# UV_Watch_1.net
KiCad netlist of a schematic drawn in Altium Designer
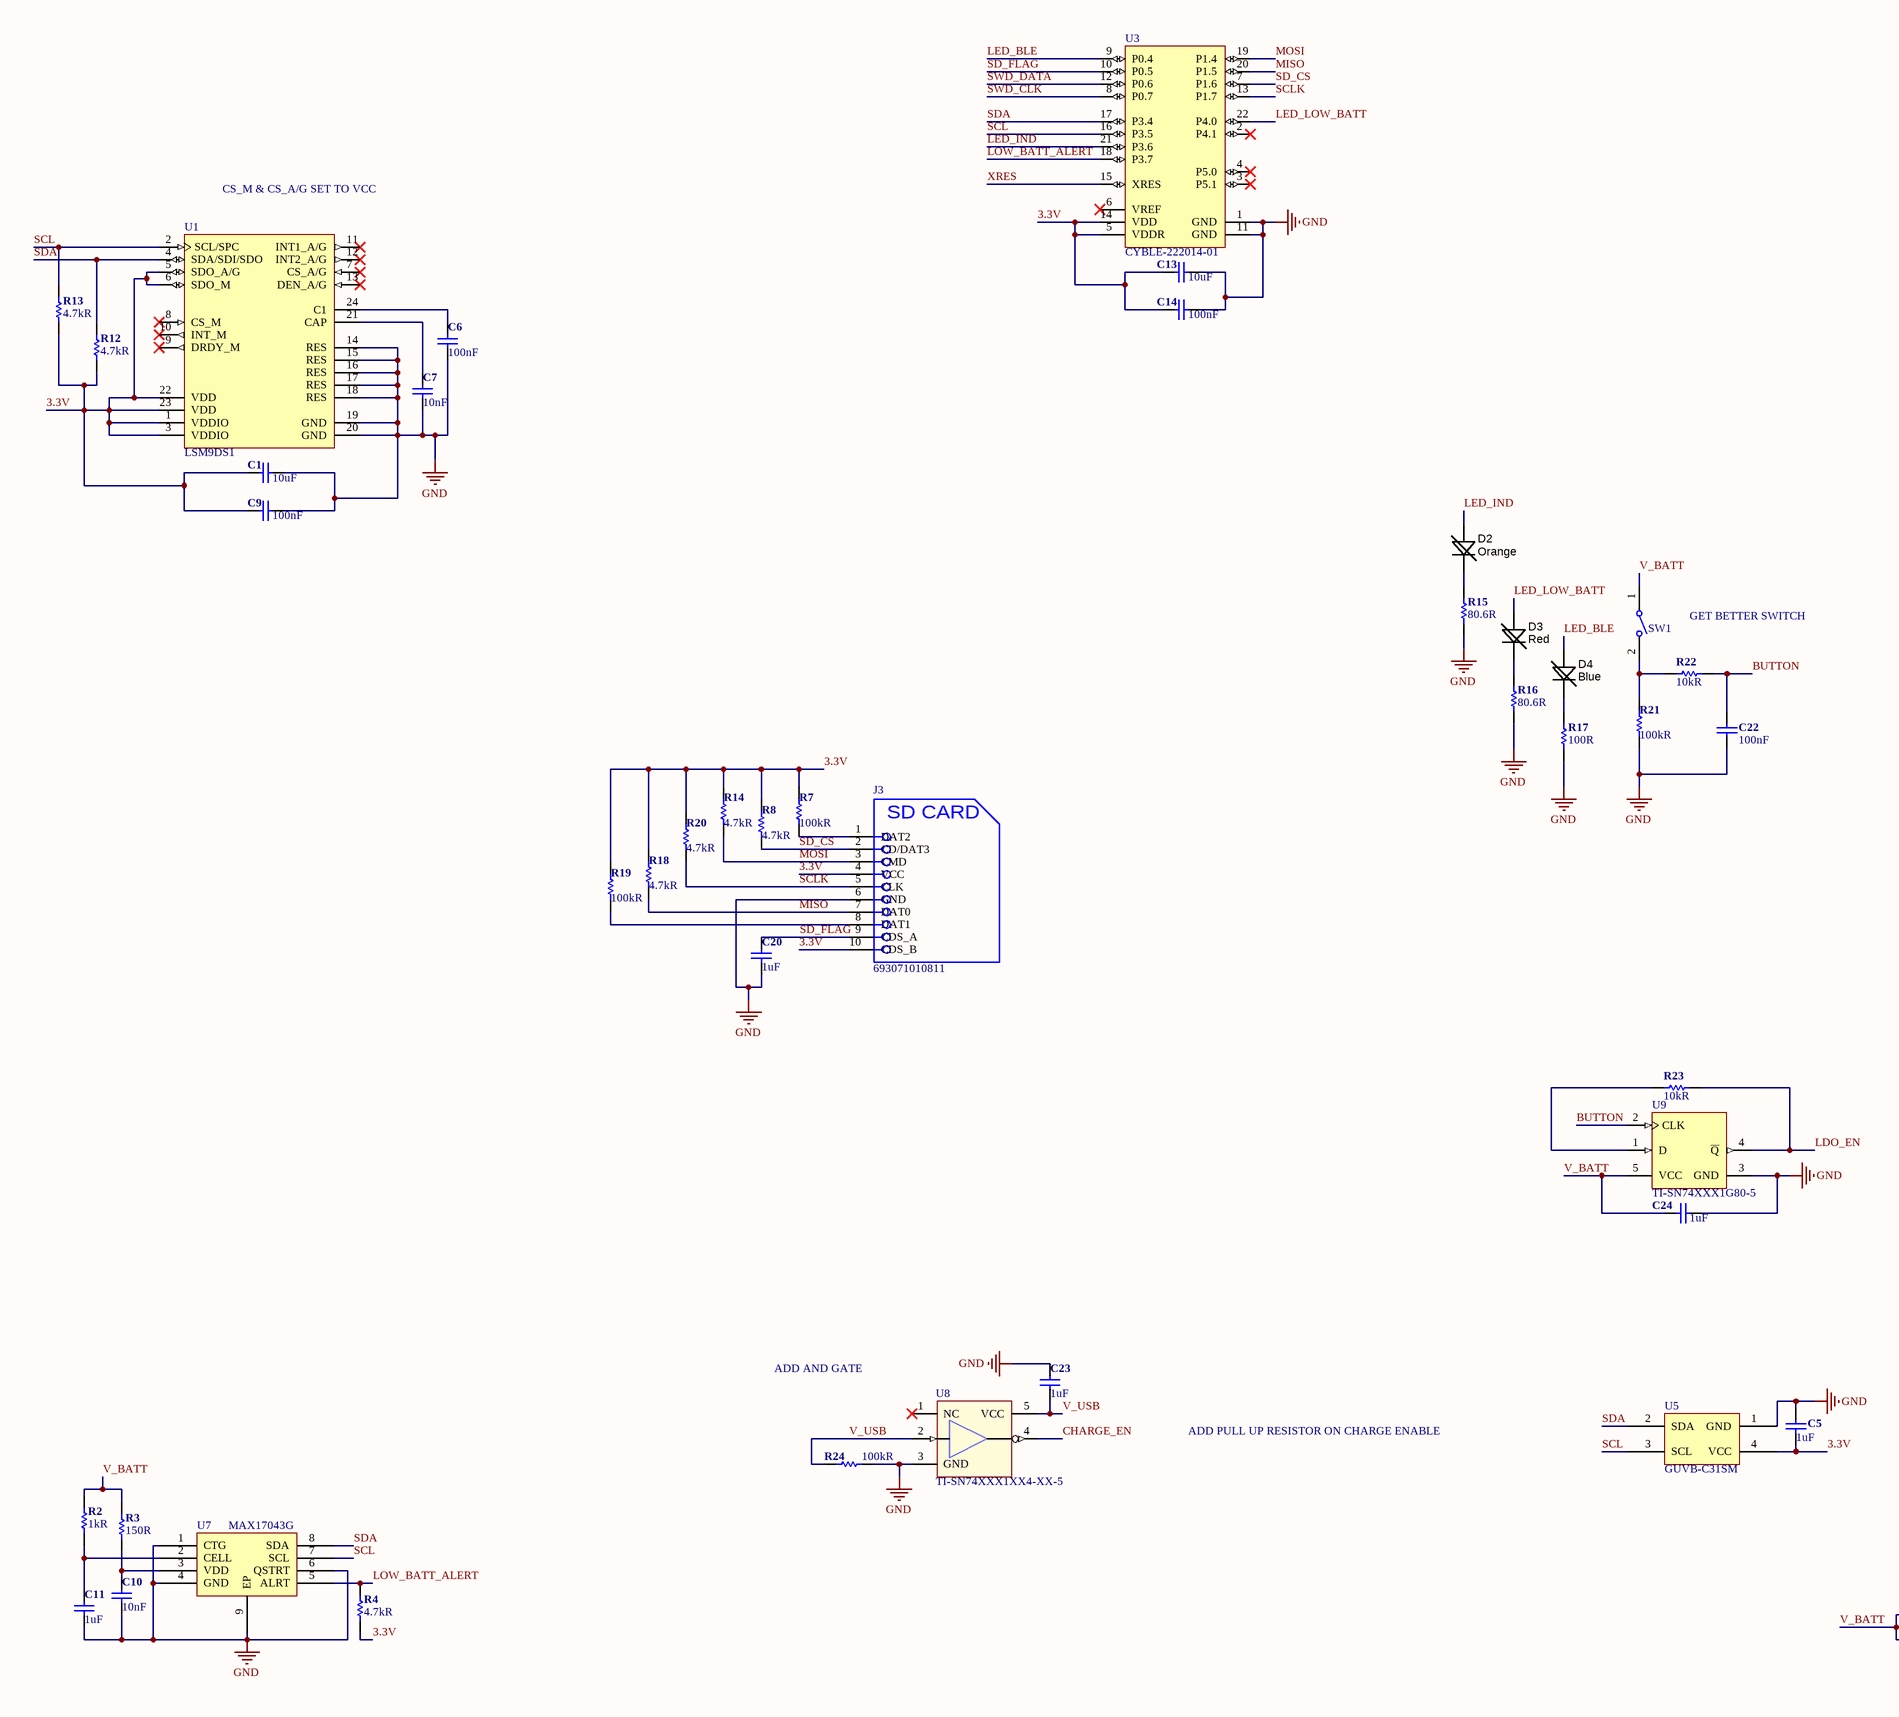
[diagram p0: UV_Watch_1.SchDoc, left]
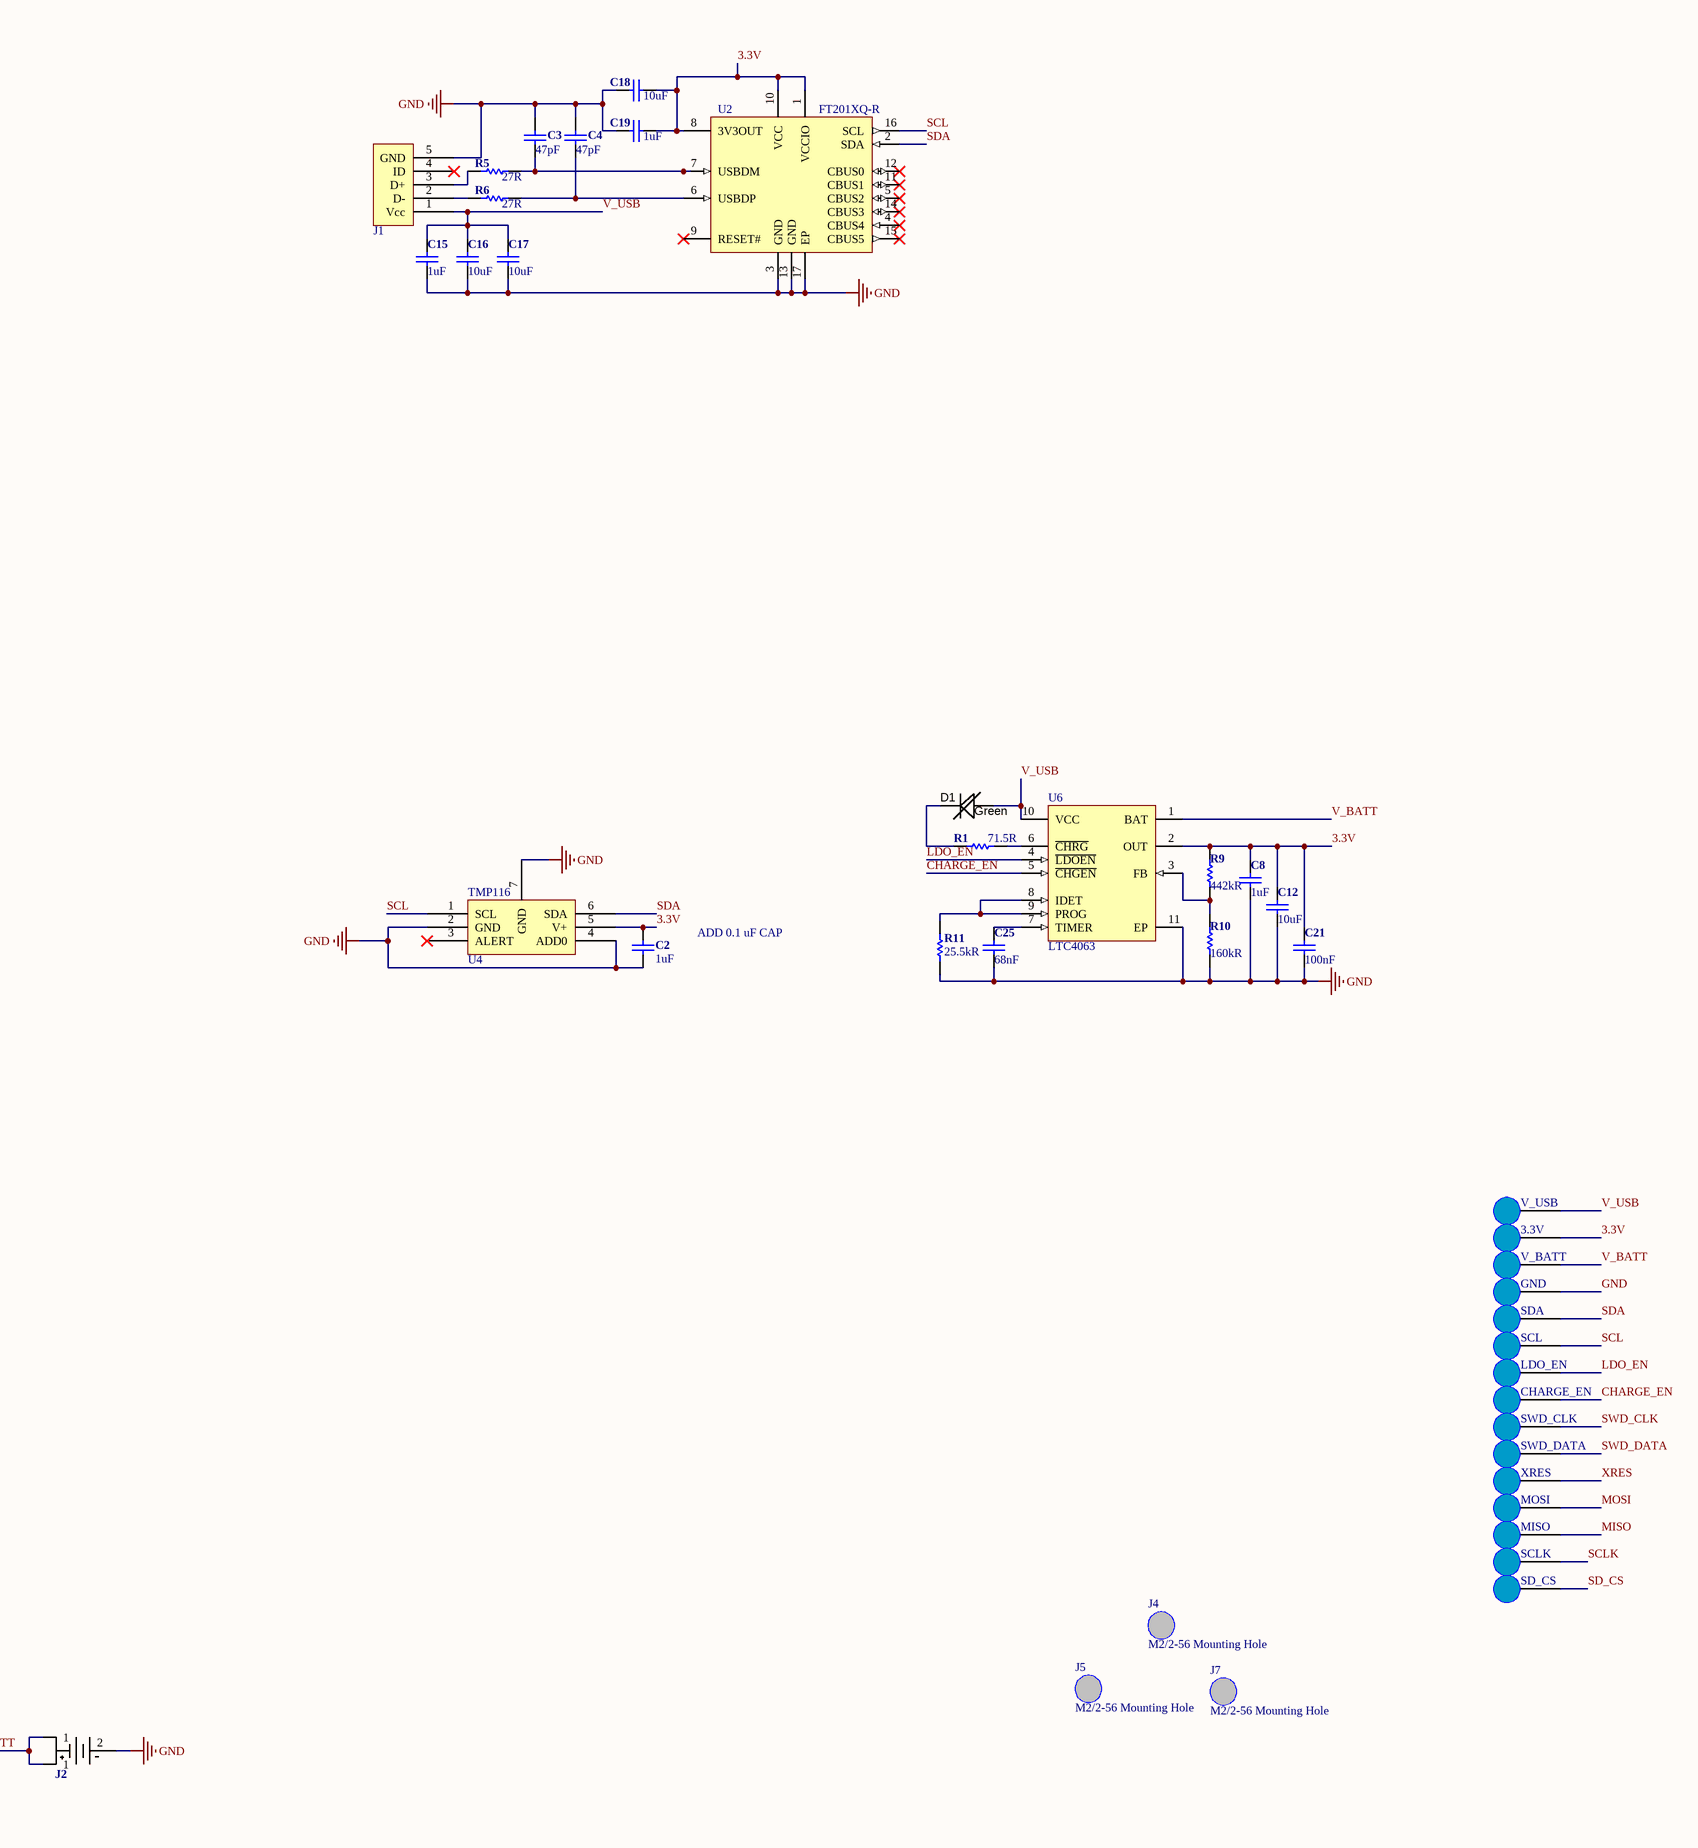
[diagram p1: UV_Watch_1.SchDoc, right]

(export (version "E")
  (design (tool "Eeschema 10.0.6"))
  (components
    (comp (ref "3.3V")
      (value "Pogo-Pin Pad")
      (footprint "Pogo-Pin-Hole")
      (fields (field (name "MANUFACTURER") "Harwin") (field (name "MANUFACTURER PART NUMBER") "P13-2123"))
      (libsource (lib "UVS-Schlib") (part "Pogo-Pin Pad"))
    )
    (comp (ref "C1")
      (value "10uF")
      (footprint "CAP-0805(2012)-R")
      (description "___ OHM ___ mW 0805(2012) SMD")
      (fields
        (field (name "MANUFACTURER") "Yageo")
        (field (name "MANUFACTURER PART NUMBER") "CC0805ZKY5V5BB106")
      )
      (libsource (lib "Glove") (part "C-0805(2012)"))
    )
    (comp (ref "C2")
      (value "1uF")
      (footprint "CAP-0805(2012)-R")
      (description "___ OHM ___ mW 0805(2012) SMD")
      (fields
        (field (name "MANUFACTURER") "Yageo")
        (field (name "MANUFACTURER PART NUMBER") "CC0805KKX7R5BB105")
      )
      (libsource (lib "Glove") (part "C-0805(2012)"))
    )
    (comp (ref "C3")
      (value "47pF")
      (footprint "CAP-0805(2012)-R")
      (description "___ OHM ___ mW 0805(2012) SMD")
      (fields
        (field (name "MANUFACTURER") "Vishay Vitramon")
        (field (name "MANUFACTURER PART NUMBER") "VJ0805A470GXQPW1BC")
      )
      (libsource (lib "Glove") (part "C-0805(2012)"))
    )
    (comp (ref "C4")
      (value "47pF")
      (footprint "CAP-0805(2012)-R")
      (description "___ OHM ___ mW 0805(2012) SMD")
      (fields
        (field (name "MANUFACTURER") "Vishay Vitramon")
        (field (name "MANUFACTURER PART NUMBER") "VJ0805A470GXQPW1BC")
      )
      (libsource (lib "Glove") (part "C-0805(2012)"))
    )
    (comp (ref "C5")
      (value "1uF")
      (footprint "CAP-0805(2012)-R")
      (description "___ OHM ___ mW 0805(2012) SMD")
      (fields
        (field (name "MANUFACTURER") "Yageo")
        (field (name "MANUFACTURER PART NUMBER") "CC0805KKX7R5BB105")
      )
      (libsource (lib "Glove") (part "C-0805(2012)"))
    )
    (comp (ref "C6")
      (value "100nF")
      (footprint "CAP-0805(2012)-R")
      (description "___ OHM ___ mW 0805(2012) SMD")
      (fields
        (field (name "MANUFACTURER") "Wurth Electronics")
        (field (name "MANUFACTURER PART NUMBER") "885012207016")
      )
      (libsource (lib "Glove") (part "C-0805(2012)"))
    )
    (comp (ref "C7")
      (value "10nF")
      (footprint "CAP-0805(2012)-R")
      (description "___ OHM ___ mW 0805(2012) SMD")
      (fields
        (field (name "MANUFACTURER") "Vishay Vitramon")
        (field (name "MANUFACTURER PART NUMBER") "VJ0805Y103MXQPW1BC")
      )
      (libsource (lib "Glove") (part "C-0805(2012)"))
    )
    (comp (ref "C8")
      (value "1uF")
      (footprint "CAP-0805(2012)-R")
      (description "___ OHM ___ mW 0805(2012) SMD")
      (fields
        (field (name "MANUFACTURER") "Yageo")
        (field (name "MANUFACTURER PART NUMBER") "CC0805KKX7R5BB105")
      )
      (libsource (lib "Glove") (part "C-0805(2012)"))
    )
    (comp (ref "C9")
      (value "100nF")
      (footprint "CAP-0805(2012)-R")
      (description "___ OHM ___ mW 0805(2012) SMD")
      (fields
        (field (name "MANUFACTURER") "Wurth Electronics")
        (field (name "MANUFACTURER PART NUMBER") "885012207016")
      )
      (libsource (lib "Glove") (part "C-0805(2012)"))
    )
    (comp (ref "C10")
      (value "10nF")
      (footprint "CAP-0805(2012)-R")
      (description "___ OHM ___ mW 0805(2012) SMD")
      (fields
        (field (name "MANUFACTURER") "Vishay Vitramon")
        (field (name "MANUFACTURER PART NUMBER") "VJ0805Y103MXQPW1BC")
      )
      (libsource (lib "Glove") (part "C-0805(2012)"))
    )
    (comp (ref "C11")
      (value "1uF")
      (footprint "CAP-0805(2012)-R")
      (description "___ OHM ___ mW 0805(2012) SMD")
      (fields
        (field (name "MANUFACTURER") "Yageo")
        (field (name "MANUFACTURER PART NUMBER") "CC0805KKX7R5BB105")
      )
      (libsource (lib "Glove") (part "C-0805(2012)"))
    )
    (comp (ref "C12")
      (value "10uF")
      (footprint "CAP-0805(2012)-R")
      (description "___ OHM ___ mW 0805(2012) SMD")
      (fields
        (field (name "MANUFACTURER") "Yageo")
        (field (name "MANUFACTURER PART NUMBER") "CC0805ZKY5V5BB106")
      )
      (libsource (lib "Glove") (part "C-0805(2012)"))
    )
    (comp (ref "C13")
      (value "10uF")
      (footprint "CAP-0805(2012)-R")
      (description "___ OHM ___ mW 0805(2012) SMD")
      (fields
        (field (name "MANUFACTURER") "Yageo")
        (field (name "MANUFACTURER PART NUMBER") "CC0805ZKY5V5BB106")
      )
      (libsource (lib "Glove") (part "C-0805(2012)"))
    )
    (comp (ref "C14")
      (value "100nF")
      (footprint "CAP-0805(2012)-R")
      (description "___ OHM ___ mW 0805(2012) SMD")
      (fields
        (field (name "MANUFACTURER") "Wurth Electronics")
        (field (name "MANUFACTURER PART NUMBER") "885012207016")
      )
      (libsource (lib "Glove") (part "C-0805(2012)"))
    )
    (comp (ref "C15")
      (value "1uF")
      (footprint "CAP-0805(2012)-R")
      (description "___ OHM ___ mW 0805(2012) SMD")
      (fields
        (field (name "MANUFACTURER") "Yageo")
        (field (name "MANUFACTURER PART NUMBER") "CC0805KKX7R5BB105")
      )
      (libsource (lib "Glove") (part "C-0805(2012)"))
    )
    (comp (ref "C16")
      (value "10uF")
      (footprint "CAP-0805(2012)-R")
      (description "___ OHM ___ mW 0805(2012) SMD")
      (fields
        (field (name "MANUFACTURER") "Yageo")
        (field (name "MANUFACTURER PART NUMBER") "CC0805ZKY5V5BB106")
      )
      (libsource (lib "Glove") (part "C-0805(2012)"))
    )
    (comp (ref "C17")
      (value "10uF")
      (footprint "CAP-0805(2012)-R")
      (description "___ OHM ___ mW 0805(2012) SMD")
      (fields
        (field (name "MANUFACTURER") "Yageo")
        (field (name "MANUFACTURER PART NUMBER") "CC0805ZKY5V5BB106")
      )
      (libsource (lib "Glove") (part "C-0805(2012)"))
    )
    (comp (ref "C18")
      (value "10uF")
      (footprint "CAP-0805(2012)-R")
      (description "___ OHM ___ mW 0805(2012) SMD")
      (fields
        (field (name "MANUFACTURER") "Yageo")
        (field (name "MANUFACTURER PART NUMBER") "CC0805ZKY5V5BB106")
      )
      (libsource (lib "Glove") (part "C-0805(2012)"))
    )
    (comp (ref "C19")
      (value "1uF")
      (footprint "CAP-0805(2012)-R")
      (description "___ OHM ___ mW 0805(2012) SMD")
      (fields
        (field (name "MANUFACTURER") "Yageo")
        (field (name "MANUFACTURER PART NUMBER") "CC0805KKX7R5BB105")
      )
      (libsource (lib "Glove") (part "C-0805(2012)"))
    )
    (comp (ref "C20")
      (value "1uF")
      (footprint "CAP-0805(2012)-R")
      (description "___ OHM ___ mW 0805(2012) SMD")
      (fields
        (field (name "MANUFACTURER") "Yageo")
        (field (name "MANUFACTURER PART NUMBER") "CC0805KKX7R5BB105")
      )
      (libsource (lib "Glove") (part "C-0805(2012)"))
    )
    (comp (ref "C21")
      (value "100nF")
      (footprint "CAP-0805(2012)-R")
      (description "___ OHM ___ mW 0805(2012) SMD")
      (fields
        (field (name "MANUFACTURER") "Wurth Electronics")
        (field (name "MANUFACTURER PART NUMBER") "885012207016")
      )
      (libsource (lib "Glove") (part "C-0805(2012)"))
    )
    (comp (ref "C22")
      (value "100nF")
      (footprint "CAP-0805(2012)-R")
      (description "___ OHM ___ mW 0805(2012) SMD")
      (fields
        (field (name "MANUFACTURER") "Wurth Electronics")
        (field (name "MANUFACTURER PART NUMBER") "885012207016")
      )
      (libsource (lib "Glove") (part "C-0805(2012)"))
    )
    (comp (ref "C23")
      (value "1uF")
      (footprint "CAP-0805(2012)-R")
      (description "___ OHM ___ mW 0805(2012) SMD")
      (fields
        (field (name "MANUFACTURER") "Yageo")
        (field (name "MANUFACTURER PART NUMBER") "CC0805KKX7R5BB105")
      )
      (libsource (lib "UVS-Schlib") (part "C-0805(2012)"))
    )
    (comp (ref "C24")
      (value "1uF")
      (footprint "CAP-0805(2012)-R")
      (description "___ OHM ___ mW 0805(2012) SMD")
      (fields
        (field (name "MANUFACTURER") "Yageo")
        (field (name "MANUFACTURER PART NUMBER") "CC0805KKX7R5BB105")
      )
      (libsource (lib "UVS-Schlib") (part "C-0805(2012)"))
    )
    (comp (ref "C25")
      (value "68nF")
      (footprint "CAP-0805(2012)-R")
      (description "___ OHM ___ mW 0805(2012) SMD")
      (fields
        (field (name "MANUFACTURER") "Wurth Electronics")
        (field (name "MANUFACTURER PART NUMBER") "885012207044")
      )
      (libsource (lib "UVS-Schlib") (part "C-0805(2012)"))
    )
    (comp (ref "CHARGE_EN")
      (value "Pogo-Pin Pad")
      (footprint "Pogo-Pin-Hole")
      (fields (field (name "MANUFACTURER") "Harwin") (field (name "MANUFACTURER PART NUMBER") "P13-2123"))
      (libsource (lib "UVS-Schlib") (part "Pogo-Pin Pad"))
    )
    (comp (ref "D1")
      (value "Green")
      (footprint "LED-0805-A")
      (description "LED, 0805 SMD")
      (fields
        (field (name "MANUFACTURER") "Kingbright")
        (field (name "MANUFACTURER PART NUMBER") "APHCM2012CGCK-F01")
      )
      (libsource (lib "UVS-Schlib") (part "LED_0805"))
    )
    (comp (ref "D2")
      (value "Orange")
      (footprint "LED-0805-A")
      (description "LED, 0805 SMD")
      (fields
        (field (name "MANUFACTURER") "Kingbright")
        (field (name "MANUFACTURER PART NUMBER") "APT2012LSECK/J4-PRV")
      )
      (libsource (lib "UVS-Schlib") (part "LED_0805"))
    )
    (comp (ref "D3")
      (value "Red")
      (footprint "LED-0805-A")
      (description "LED, 0805 SMD")
      (fields
        (field (name "MANUFACTURER") "Kingbright")
        (field (name "MANUFACTURER PART NUMBER") "APT2012LSECK/J3-PRV")
      )
      (libsource (lib "UVS-Schlib") (part "LED_0805"))
    )
    (comp (ref "D4")
      (value "Blue")
      (footprint "LED-0805-A")
      (description "LED, 0805 SMD")
      (fields
        (field (name "MANUFACTURER") "Kingbright")
        (field (name "MANUFACTURER PART NUMBER") "APTD2012LQBC/D")
      )
      (libsource (lib "UVS-Schlib") (part "LED_0805"))
    )
    (comp (ref "GND")
      (value "Pogo-Pin Pad")
      (footprint "Pogo-Pin-Hole")
      (fields (field (name "MANUFACTURER") "Harwin") (field (name "MANUFACTURER PART NUMBER") "P13-2123"))
      (libsource (lib "UVS-Schlib") (part "Pogo-Pin Pad"))
    )
    (comp (ref "J1")
      (value "USB")
      (footprint "USB_Connector_5P_MICRO_USB_FCI")
      (description "USB_Connector_5P_MICRO_USB_FCI")
      (fields
        (field (name "MANUFACTURER") "Amphenol FCI")
        (field (name "MANUFACTURER PART NUMBER") "10118194-0001LF")
      )
      (libsource (lib "Glove") (part "USB"))
    )
    (comp (ref "J2")
      (value "Header 2 pin")
      (footprint "LINX_BATT_HLDR")
      (description "Header, 2 pin, .1 pitch")
      (fields (field (name "MANUFACTURER") "Linx") (field (name "MANUFACTURER PART NUMBER") "BAT-HLD-001"))
      (libsource (lib "UVS-Schlib") (part "BAT-HLD-001"))
    )
    (comp (ref "J3")
      (value "693071010811")
      (footprint "693071010811")
      (description "Wurth CONN MICRO SD CARD PUSH-PUSH R/A")
      (fields (field (name "MANUFACTURER") "Wurth Electronics"))
      (libsource (lib "UVS-Schlib") (part "693071010811"))
    )
    (comp (ref "J4")
      (value "M2/2-56 Mounting Hole")
      (footprint "Mounting Hole")
      (libsource (lib "UVS-Schlib") (part "M2/2-56 Mounting Hole"))
    )
    (comp (ref "J5")
      (value "M2/2-56 Mounting Hole")
      (footprint "Mounting Hole")
      (libsource (lib "UVS-Schlib") (part "M2/2-56 Mounting Hole"))
    )
    (comp (ref "J7")
      (value "M2/2-56 Mounting Hole")
      (footprint "Mounting Hole")
      (libsource (lib "UVS-Schlib") (part "M2/2-56 Mounting Hole"))
    )
    (comp (ref "LDO_EN")
      (value "Pogo-Pin Pad")
      (footprint "Pogo-Pin-Hole")
      (fields (field (name "MANUFACTURER") "Harwin") (field (name "MANUFACTURER PART NUMBER") "P13-2123"))
      (libsource (lib "UVS-Schlib") (part "Pogo-Pin Pad"))
    )
    (comp (ref "MISO")
      (value "Pogo-Pin Pad")
      (footprint "Pogo-Pin-Hole")
      (fields (field (name "MANUFACTURER") "Harwin") (field (name "MANUFACTURER PART NUMBER") "P13-2123"))
      (libsource (lib "UVS-Schlib") (part "Pogo-Pin Pad"))
    )
    (comp (ref "MOSI")
      (value "Pogo-Pin Pad")
      (footprint "Pogo-Pin-Hole")
      (fields (field (name "MANUFACTURER") "Harwin") (field (name "MANUFACTURER PART NUMBER") "P13-2123"))
      (libsource (lib "UVS-Schlib") (part "Pogo-Pin Pad"))
    )
    (comp (ref "R1")
      (value "71.5R")
      (footprint "R-0805(2012)-R")
      (description "___ OHM ___ mW 0805(2012) SMD")
      (fields
        (field (name "MANUFACTURER") "Yageo")
        (field (name "MANUFACTURER PART NUMBER") "RC0805FR-0771R5L")
      )
      (libsource (lib "Glove") (part "R-0805(2012)"))
    )
    (comp (ref "R2")
      (value "1kR")
      (footprint "R-0805(2012)-R")
      (description "___ OHM ___ mW 0805(2012) SMD")
      (fields
        (field (name "MANUFACTURER") "Yageo")
        (field (name "MANUFACTURER PART NUMBER") "AC0805JR-071KL")
      )
      (libsource (lib "UVS-Schlib") (part "R-0805(2012)"))
    )
    (comp (ref "R3")
      (value "150R")
      (footprint "R-0805(2012)-R")
      (description "___ OHM ___ mW 0805(2012) SMD")
      (fields
        (field (name "MANUFACTURER") "Yageo")
        (field (name "MANUFACTURER PART NUMBER") "RC0805FR-07150RL")
      )
      (libsource (lib "UVS-Schlib") (part "R-0805(2012)"))
    )
    (comp (ref "R4")
      (value "4.7kR")
      (footprint "R-0805(2012)-R")
      (description "___ OHM ___ mW 0805(2012) SMD")
      (fields
        (field (name "MANUFACTURER") "Yageo")
        (field (name "MANUFACTURER PART NUMBER") "AC0805JR-074K7L")
      )
      (libsource (lib "UVS-Schlib") (part "R-0805(2012)"))
    )
    (comp (ref "R5")
      (value "27R")
      (footprint "R-0805(2012)-R")
      (description "___ OHM ___ mW 0805(2012) SMD")
      (fields
        (field (name "MANUFACTURER") "Yageo")
        (field (name "MANUFACTURER PART NUMBER") "RC0805JR-0727RL")
      )
      (libsource (lib "Glove") (part "R-0805(2012)"))
    )
    (comp (ref "R6")
      (value "27R")
      (footprint "R-0805(2012)-R")
      (description "___ OHM ___ mW 0805(2012) SMD")
      (fields
        (field (name "MANUFACTURER") "Yageo")
        (field (name "MANUFACTURER PART NUMBER") "RC0805JR-0727RL")
      )
      (libsource (lib "Glove") (part "R-0805(2012)"))
    )
    (comp (ref "R7")
      (value "100kR")
      (footprint "R-0805(2012)-R")
      (description "___ OHM ___ mW 0805(2012) SMD")
      (fields
        (field (name "MANUFACTURER") "Yageo")
        (field (name "MANUFACTURER PART NUMBER") "RC0805FR-07100KL")
      )
      (libsource (lib "Glove") (part "R-0805(2012)"))
    )
    (comp (ref "R8")
      (value "4.7kR")
      (footprint "R-0805(2012)-R")
      (description "___ OHM ___ mW 0805(2012) SMD")
      (fields
        (field (name "MANUFACTURER") "Yageo")
        (field (name "MANUFACTURER PART NUMBER") "AC0805JR-074K7L")
      )
      (libsource (lib "Glove") (part "R-0805(2012)"))
    )
    (comp (ref "R9")
      (value "442kR")
      (footprint "R-0805(2012)-R")
      (description "___ OHM ___ mW 0805(2012) SMD")
      (fields
        (field (name "MANUFACTURER") "Yageo")
        (field (name "MANUFACTURER PART NUMBER") "RC0805FR-07442KL")
      )
      (libsource (lib "Glove") (part "R-0805(2012)"))
    )
    (comp (ref "R10")
      (value "160kR")
      (footprint "R-0805(2012)-R")
      (description "___ OHM ___ mW 0805(2012) SMD")
      (fields
        (field (name "MANUFACTURER") "Yageo")
        (field (name "MANUFACTURER PART NUMBER") "RC0805FR-07160KL")
      )
      (libsource (lib "Glove") (part "R-0805(2012)"))
    )
    (comp (ref "R11")
      (value "25.5kR")
      (footprint "R-0805(2012)-R")
      (description "___ OHM ___ mW 0805(2012) SMD")
      (fields
        (field (name "MANUFACTURER") "Yageo")
        (field (name "MANUFACTURER PART NUMBER") "RC0805FR-0725K5L")
      )
      (libsource (lib "Glove") (part "R-0805(2012)"))
    )
    (comp (ref "R12")
      (value "4.7kR")
      (footprint "R-0805(2012)-R")
      (description "___ OHM ___ mW 0805(2012) SMD")
      (fields
        (field (name "MANUFACTURER") "Yageo")
        (field (name "MANUFACTURER PART NUMBER") "AC0805JR-074K7L")
      )
      (libsource (lib "Glove") (part "R-0805(2012)"))
    )
    (comp (ref "R13")
      (value "4.7kR")
      (footprint "R-0805(2012)-R")
      (description "___ OHM ___ mW 0805(2012) SMD")
      (fields
        (field (name "MANUFACTURER") "Yageo")
        (field (name "MANUFACTURER PART NUMBER") "AC0805JR-074K7L")
      )
      (libsource (lib "Glove") (part "R-0805(2012)"))
    )
    (comp (ref "R14")
      (value "4.7kR")
      (footprint "R-0805(2012)-R")
      (description "___ OHM ___ mW 0805(2012) SMD")
      (fields
        (field (name "MANUFACTURER") "Yageo")
        (field (name "MANUFACTURER PART NUMBER") "AC0805JR-074K7L")
      )
      (libsource (lib "Glove") (part "R-0805(2012)"))
    )
    (comp (ref "R15")
      (value "80.6R")
      (footprint "R-0805(2012)-R")
      (description "___ OHM ___ mW 0805(2012) SMD")
      (fields
        (field (name "MANUFACTURER") "Yageo")
        (field (name "MANUFACTURER PART NUMBER") "RC0805FR-0780R6L")
      )
      (libsource (lib "UVS-Schlib") (part "R-0805(2012)"))
    )
    (comp (ref "R16")
      (value "80.6R")
      (footprint "R-0805(2012)-R")
      (description "___ OHM ___ mW 0805(2012) SMD")
      (fields
        (field (name "MANUFACTURER") "Yageo")
        (field (name "MANUFACTURER PART NUMBER") "RC0805FR-0780R6L")
      )
      (libsource (lib "UVS-Schlib") (part "R-0805(2012)"))
    )
    (comp (ref "R17")
      (value "100R")
      (footprint "R-0805(2012)-R")
      (description "___ OHM ___ mW 0805(2012) SMD")
      (fields
        (field (name "MANUFACTURER") "Yageo")
        (field (name "MANUFACTURER PART NUMBER") "AC0805FR-07100RL")
      )
      (libsource (lib "UVS-Schlib") (part "R-0805(2012)"))
    )
    (comp (ref "R18")
      (value "4.7kR")
      (footprint "R-0805(2012)-R")
      (description "___ OHM ___ mW 0805(2012) SMD")
      (fields
        (field (name "MANUFACTURER") "Yageo")
        (field (name "MANUFACTURER PART NUMBER") "AC0805JR-074K7L")
      )
      (libsource (lib "Glove") (part "R-0805(2012)"))
    )
    (comp (ref "R19")
      (value "100kR")
      (footprint "R-0805(2012)-R")
      (description "___ OHM ___ mW 0805(2012) SMD")
      (fields
        (field (name "MANUFACTURER") "Yageo")
        (field (name "MANUFACTURER PART NUMBER") "RC0805FR-07100KL")
      )
      (libsource (lib "Glove") (part "R-0805(2012)"))
    )
    (comp (ref "R20")
      (value "4.7kR")
      (footprint "R-0805(2012)-R")
      (description "___ OHM ___ mW 0805(2012) SMD")
      (fields
        (field (name "MANUFACTURER") "Yageo")
        (field (name "MANUFACTURER PART NUMBER") "AC0805JR-074K7L")
      )
      (libsource (lib "Glove") (part "R-0805(2012)"))
    )
    (comp (ref "R21")
      (value "100kR")
      (footprint "R-0805(2012)-R")
      (description "___ OHM ___ mW 0805(2012) SMD")
      (fields
        (field (name "MANUFACTURER") "Yageo")
        (field (name "MANUFACTURER PART NUMBER") "RC0805FR-07100KL")
      )
      (libsource (lib "Glove") (part "R-0805(2012)"))
    )
    (comp (ref "R22")
      (value "10kR")
      (footprint "R-0805(2012)-R")
      (description "___ OHM ___ mW 0805(2012) SMD")
      (fields
        (field (name "MANUFACTURER") "Yageo")
        (field (name "MANUFACTURER PART NUMBER") "AC0805FR-0710KL")
      )
      (libsource (lib "UVS-Schlib") (part "R-0805(2012)"))
    )
    (comp (ref "R23")
      (value "10kR")
      (footprint "R-0805(2012)-R")
      (description "___ OHM ___ mW 0805(2012) SMD")
      (fields
        (field (name "MANUFACTURER") "Yageo")
        (field (name "MANUFACTURER PART NUMBER") "AC0805FR-0710KL")
      )
      (libsource (lib "UVS-Schlib") (part "R-0805(2012)"))
    )
    (comp (ref "R24")
      (value "100kR")
      (footprint "R-0805(2012)-R")
      (description "___ OHM ___ mW 0805(2012) SMD")
      (fields
        (field (name "MANUFACTURER") "Yageo")
        (field (name "MANUFACTURER PART NUMBER") "RC0805FR-07100KL")
      )
      (libsource (lib "UVS-Schlib") (part "R-0805(2012)"))
    )
    (comp (ref "SCL")
      (value "Pogo-Pin Pad")
      (footprint "Pogo-Pin-Hole")
      (fields (field (name "MANUFACTURER") "Harwin") (field (name "MANUFACTURER PART NUMBER") "P13-2123"))
      (libsource (lib "UVS-Schlib") (part "Pogo-Pin Pad"))
    )
    (comp (ref "SCLK")
      (value "Pogo-Pin Pad")
      (footprint "Pogo-Pin-Hole")
      (fields (field (name "MANUFACTURER") "Harwin") (field (name "MANUFACTURER PART NUMBER") "P13-2123"))
      (libsource (lib "UVS-Schlib") (part "Pogo-Pin Pad"))
    )
    (comp (ref "SDA")
      (value "Pogo-Pin Pad")
      (footprint "Pogo-Pin-Hole")
      (fields (field (name "MANUFACTURER") "Harwin") (field (name "MANUFACTURER PART NUMBER") "P13-2123"))
      (libsource (lib "UVS-Schlib") (part "Pogo-Pin Pad"))
    )
    (comp (ref "SD_CS")
      (value "Pogo-Pin Pad")
      (footprint "Pogo-Pin-Hole")
      (fields (field (name "MANUFACTURER") "Harwin") (field (name "MANUFACTURER PART NUMBER") "P13-2123"))
      (libsource (lib "UVS-Schlib") (part "Pogo-Pin Pad"))
    )
    (comp (ref "SW1")
      (value "SW-SPST-2_C")
      (footprint "OMRON-B3U-3000P_V")
      (fields (field (name "MANUFACTURER") "Omron") (field (name "MANUFACTURER PART NUMBER") "B3U-3000P"))
      (libsource (lib "UVS-Schlib") (part "SW-SPST-2_C"))
    )
    (comp (ref "SWD_CLK")
      (value "Pogo-Pin Pad")
      (footprint "Pogo-Pin-Hole")
      (fields (field (name "MANUFACTURER") "Harwin") (field (name "MANUFACTURER PART NUMBER") "P13-2123"))
      (libsource (lib "UVS-Schlib") (part "Pogo-Pin Pad"))
    )
    (comp (ref "SWD_DATA")
      (value "Pogo-Pin Pad")
      (footprint "Pogo-Pin-Hole")
      (fields (field (name "MANUFACTURER") "Harwin") (field (name "MANUFACTURER PART NUMBER") "P13-2123"))
      (libsource (lib "UVS-Schlib") (part "Pogo-Pin Pad"))
    )
    (comp (ref "U1")
      (value "LSM9DS1")
      (footprint "STM-LGA-24")
      (fields
        (field (name "MANUFACTURER") "STMicroelectronics")
        (field (name "MANUFACTURER PART NUMBER") "LSM9DS1TR")
      )
      (libsource (lib "UVS-Schlib") (part "LSM9DS1"))
    )
    (comp (ref "U2")
      (value "FT201XQ-R")
      (footprint "QFN-16")
      (fields (field (name "MANUFACTURER") "FTDI"))
      (libsource (lib "UVS-Schlib") (part "FT201XQ-R"))
    )
    (comp (ref "U3")
      (value "CYBLE-222014-01")
      (footprint "CYP-SP21_V")
      (fields (field (name "MANUFACTURER") "Cypress"))
      (libsource (lib "UVS-Schlib") (part "CYBLE-222014-01"))
    )
    (comp (ref "U4")
      (value "TMP116")
      (footprint "WSON-6")
      (fields
        (field (name "MANUFACTURER") "Texas Instruments")
        (field (name "MANUFACTURER PART NUMBER") "TMP116AIDRVT")
      )
      (libsource (lib "UVS-Schlib") (part "TMP116"))
    )
    (comp (ref "U5")
      (value "GUVB-C31SM")
      (footprint "GUVB-C31SM")
      (libsource (lib "UVS-Schlib") (part "GUVB-C31SM"))
    )
    (comp (ref "U6")
      (value "LTC4063")
      (footprint "LT-DD-10_V")
      (fields
        (field (name "MANUFACTURER") "Analog Devices / Linear Technology")
        (field (name "MANUFACTURER PART NUMBER") "LTC4063EDD#PBF")
      )
      (libsource (lib "UVS-Schlib") (part "LTC4063"))
    )
    (comp (ref "U7")
      (value "MAX17043G")
      (footprint "TDFN-MN8")
      (fields (field (name "MANUFACTURER") "Maxim") (field (name "MANUFACTURER PART NUMBER") "MAX17043G+T"))
      (libsource (lib "UVS-Schlib") (part "MAX17043G"))
    )
    (comp (ref "U8")
      (value "TI-SN74XXX1XX4-XX-5")
      (footprint "DBV0005A_M")
      (description "SN74AHC1G04DBVR")
      (fields (field (name "MANUFACTURER") "Texas Instruments"))
      (libsource (lib "UVS-Schlib") (part "TI-SN74XXX1XX4-XX-5"))
    )
    (comp (ref "U9")
      (value "TI-SN74XXX1G80-5")
      (footprint "DBV0005A_L")
      (fields
        (field (name "MANUFACTURER") "Texas Instruments")
        (field (name "MANUFACTURER PART NUMBER") "SN74AUP1G80DBVR")
      )
      (libsource (lib "UVS-Schlib") (part "TI-SN74XXX1G80-5"))
    )
    (comp (ref "V_BATT")
      (value "Pogo-Pin Pad")
      (footprint "Pogo-Pin-Hole")
      (fields (field (name "MANUFACTURER") "Harwin") (field (name "MANUFACTURER PART NUMBER") "P13-2123"))
      (libsource (lib "UVS-Schlib") (part "Pogo-Pin Pad"))
    )
    (comp (ref "V_USB")
      (value "Pogo-Pin Pad")
      (footprint "Pogo-Pin-Hole")
      (fields (field (name "MANUFACTURER") "Harwin") (field (name "MANUFACTURER PART NUMBER") "P13-2123"))
      (libsource (lib "UVS-Schlib") (part "Pogo-Pin Pad"))
    )
    (comp (ref "XRES")
      (value "Pogo-Pin Pad")
      (footprint "Pogo-Pin-Hole")
      (fields (field (name "MANUFACTURER") "Harwin") (field (name "MANUFACTURER PART NUMBER") "P13-2123"))
      (libsource (lib "UVS-Schlib") (part "Pogo-Pin Pad"))
    )
  )
  (nets
    (net (code "1") (name "/3.3V") (class "Default")
      (node (ref "3.3V") (pin "1") (pinfunction "1_1") (pintype "passive"))
      (node (ref "C1") (pin "1") (pinfunction "1_1") (pintype "passive"))
      (node (ref "C12") (pin "1") (pinfunction "1_1") (pintype "passive"))
      (node (ref "C13") (pin "1") (pinfunction "1_1") (pintype "passive"))
      (node (ref "C14") (pin "1") (pinfunction "1_1") (pintype "passive"))
      (node (ref "C18") (pin "1") (pinfunction "1_1") (pintype "passive"))
      (node (ref "C19") (pin "2") (pinfunction "2_2") (pintype "passive"))
      (node (ref "C2") (pin "1") (pinfunction "1_1") (pintype "passive"))
      (node (ref "C21") (pin "2") (pinfunction "2_2") (pintype "passive"))
      (node (ref "C5") (pin "2") (pinfunction "2_2") (pintype "passive"))
      (node (ref "C8") (pin "1") (pinfunction "1_1") (pintype "passive"))
      (node (ref "C9") (pin "1") (pinfunction "1_1") (pintype "passive"))
      (node (ref "J3") (pin "10") (pinfunction "CDS_B_10") (pintype "passive"))
      (node (ref "J3") (pin "4") (pinfunction "VCC_4") (pintype "passive"))
      (node (ref "R12") (pin "2") (pinfunction "2_2") (pintype "passive"))
      (node (ref "R13") (pin "1") (pinfunction "1_1") (pintype "passive"))
      (node (ref "R14") (pin "1") (pinfunction "1_1") (pintype "passive"))
      (node (ref "R18") (pin "1") (pinfunction "1_1") (pintype "passive"))
      (node (ref "R19") (pin "1") (pinfunction "1_1") (pintype "passive"))
      (node (ref "R20") (pin "1") (pinfunction "1_1") (pintype "passive"))
      (node (ref "R4") (pin "1") (pinfunction "1_1") (pintype "passive"))
      (node (ref "R7") (pin "1") (pinfunction "1_1") (pintype "passive"))
      (node (ref "R8") (pin "1") (pinfunction "1_1") (pintype "passive"))
      (node (ref "R9") (pin "2") (pinfunction "2_2") (pintype "passive"))
      (node (ref "U1") (pin "1") (pinfunction "VDDIO_1") (pintype "power_in"))
      (node (ref "U1") (pin "22") (pinfunction "VDD_22") (pintype "power_in"))
      (node (ref "U1") (pin "23") (pinfunction "VDD_23") (pintype "power_in"))
      (node (ref "U1") (pin "3") (pinfunction "VDDIO_3") (pintype "power_in"))
      (node (ref "U1") (pin "5") (pinfunction "SDO_A/G_5") (pintype "bidirectional"))
      (node (ref "U1") (pin "6") (pinfunction "SDO_M_6") (pintype "bidirectional"))
      (node (ref "U2") (pin "1") (pinfunction "VCCIO_1") (pintype "power_in"))
      (node (ref "U2") (pin "10") (pinfunction "VCC_10") (pintype "power_in"))
      (node (ref "U2") (pin "8") (pinfunction "3V3OUT_8") (pintype "power_in"))
      (node (ref "U3") (pin "14") (pinfunction "VDD_14") (pintype "power_in"))
      (node (ref "U3") (pin "5") (pinfunction "VDDR_5") (pintype "power_in"))
      (node (ref "U4") (pin "5") (pinfunction "V+_5") (pintype "passive"))
      (node (ref "U5") (pin "4") (pinfunction "VCC_4") (pintype "passive"))
      (node (ref "U6") (pin "2") (pinfunction "OUT_2") (pintype "power_in"))
    )
    (net (code "2") (name "/BUTTON") (class "Default")
      (node (ref "C22") (pin "2") (pinfunction "2_2") (pintype "passive"))
      (node (ref "R22") (pin "2") (pinfunction "2_2") (pintype "passive"))
      (node (ref "U9") (pin "2") (pinfunction "CLK_2") (pintype "input"))
    )
    (net (code "3") (name "/CHARGE_EN") (class "Default")
      (node (ref "CHARGE_EN") (pin "1") (pinfunction "1_1") (pintype "passive"))
      (node (ref "U6") (pin "5") (pinfunction "~{CHGEN}_5") (pintype "input"))
      (node (ref "U8") (pin "4") (pinfunction "Y_4") (pintype "output"))
    )
    (net (code "4") (name "/LDO_EN") (class "Default")
      (node (ref "LDO_EN") (pin "1") (pinfunction "1_1") (pintype "passive"))
      (node (ref "R23") (pin "2") (pinfunction "2_2") (pintype "passive"))
      (node (ref "U6") (pin "4") (pinfunction "~{LDOEN}_4") (pintype "input"))
      (node (ref "U9") (pin "4") (pinfunction "~{Q}_4") (pintype "output"))
    )
    (net (code "5") (name "/LED_BLE") (class "Default")
      (node (ref "D4") (pin "A") (pinfunction "A_A") (pintype "passive"))
      (node (ref "U3") (pin "9") (pinfunction "P0.4_9") (pintype "bidirectional"))
    )
    (net (code "6") (name "/LED_IND") (class "Default")
      (node (ref "D2") (pin "A") (pinfunction "A_A") (pintype "passive"))
      (node (ref "U3") (pin "21") (pinfunction "P3.6_21") (pintype "bidirectional"))
    )
    (net (code "7") (name "/LED_LOW_BATT") (class "Default")
      (node (ref "D3") (pin "A") (pinfunction "A_A") (pintype "passive"))
      (node (ref "U3") (pin "22") (pinfunction "P4.0_22") (pintype "bidirectional"))
    )
    (net (code "8") (name "/LOW_BATT_ALERT") (class "Default")
      (node (ref "R4") (pin "2") (pinfunction "2_2") (pintype "passive"))
      (node (ref "U3") (pin "18") (pinfunction "P3.7_18") (pintype "bidirectional"))
      (node (ref "U7") (pin "5") (pinfunction "ALRT_5") (pintype "passive"))
    )
    (net (code "9") (name "/MISO") (class "Default")
      (node (ref "J3") (pin "7") (pinfunction "DAT0_7") (pintype "passive"))
      (node (ref "MISO") (pin "1") (pinfunction "1_1") (pintype "passive"))
      (node (ref "R18") (pin "2") (pinfunction "2_2") (pintype "passive"))
      (node (ref "U3") (pin "20") (pinfunction "P1.5_20") (pintype "bidirectional"))
    )
    (net (code "10") (name "/MOSI") (class "Default")
      (node (ref "J3") (pin "3") (pinfunction "CMD_3") (pintype "passive"))
      (node (ref "MOSI") (pin "1") (pinfunction "1_1") (pintype "passive"))
      (node (ref "R14") (pin "2") (pinfunction "2_2") (pintype "passive"))
      (node (ref "U3") (pin "19") (pinfunction "P1.4_19") (pintype "bidirectional"))
    )
    (net (code "11") (name "/SCL") (class "Default")
      (node (ref "R13") (pin "2") (pinfunction "2_2") (pintype "passive"))
      (node (ref "SCL") (pin "1") (pinfunction "1_1") (pintype "passive"))
      (node (ref "U1") (pin "2") (pinfunction "SCL/SPC_2") (pintype "input"))
      (node (ref "U2") (pin "16") (pinfunction "SCL_16") (pintype "output"))
      (node (ref "U3") (pin "16") (pinfunction "P3.5_16") (pintype "bidirectional"))
      (node (ref "U4") (pin "1") (pinfunction "SCL_1") (pintype "passive"))
      (node (ref "U5") (pin "3") (pinfunction "SCL_3") (pintype "passive"))
      (node (ref "U7") (pin "7") (pinfunction "SCL_7") (pintype "passive"))
    )
    (net (code "12") (name "/SCLK") (class "Default")
      (node (ref "J3") (pin "5") (pinfunction "CLK_5") (pintype "passive"))
      (node (ref "R20") (pin "2") (pinfunction "2_2") (pintype "passive"))
      (node (ref "SCLK") (pin "1") (pinfunction "1_1") (pintype "passive"))
      (node (ref "U3") (pin "13") (pinfunction "P1.7_13") (pintype "bidirectional"))
    )
    (net (code "13") (name "/SDA") (class "Default")
      (node (ref "R12") (pin "1") (pinfunction "1_1") (pintype "passive"))
      (node (ref "SDA") (pin "1") (pinfunction "1_1") (pintype "passive"))
      (node (ref "U1") (pin "4") (pinfunction "SDA/SDI/SDO_4") (pintype "bidirectional"))
      (node (ref "U2") (pin "2") (pinfunction "SDA_2") (pintype "input"))
      (node (ref "U3") (pin "17") (pinfunction "P3.4_17") (pintype "bidirectional"))
      (node (ref "U4") (pin "6") (pinfunction "SDA_6") (pintype "passive"))
      (node (ref "U5") (pin "2") (pinfunction "SDA_2") (pintype "passive"))
      (node (ref "U7") (pin "8") (pinfunction "SDA_8") (pintype "passive"))
    )
    (net (code "14") (name "/SD_CS") (class "Default")
      (node (ref "J3") (pin "2") (pinfunction "CD/DAT3_2") (pintype "passive"))
      (node (ref "R8") (pin "2") (pinfunction "2_2") (pintype "passive"))
      (node (ref "SD_CS") (pin "1") (pinfunction "1_1") (pintype "passive"))
      (node (ref "U3") (pin "7") (pinfunction "P1.6_7") (pintype "bidirectional"))
    )
    (net (code "15") (name "/SD_FLAG") (class "Default")
      (node (ref "C20") (pin "1") (pinfunction "1_1") (pintype "passive"))
      (node (ref "J3") (pin "9") (pinfunction "CDS_A_9") (pintype "passive"))
      (node (ref "U3") (pin "10") (pinfunction "P0.5_10") (pintype "bidirectional"))
    )
    (net (code "16") (name "/SWD_CLK") (class "Default")
      (node (ref "SWD_CLK") (pin "1") (pinfunction "1_1") (pintype "passive"))
      (node (ref "U3") (pin "8") (pinfunction "P0.7_8") (pintype "bidirectional"))
    )
    (net (code "17") (name "/SWD_DATA") (class "Default")
      (node (ref "SWD_DATA") (pin "1") (pinfunction "1_1") (pintype "passive"))
      (node (ref "U3") (pin "12") (pinfunction "P0.6_12") (pintype "bidirectional"))
    )
    (net (code "18") (name "/V_BATT") (class "Default")
      (node (ref "C24") (pin "1") (pinfunction "1_1") (pintype "passive"))
      (node (ref "J2") (pin "1") (pinfunction "1_1") (pintype "passive"))
      (node (ref "R2") (pin "2") (pinfunction "2_2") (pintype "passive"))
      (node (ref "R3") (pin "2") (pinfunction "2_2") (pintype "passive"))
      (node (ref "SW1") (pin "1") (pinfunction "1_1") (pintype "passive"))
      (node (ref "U6") (pin "1") (pinfunction "BAT_1") (pintype "power_in"))
      (node (ref "U9") (pin "5") (pinfunction "VCC_5") (pintype "power_in"))
      (node (ref "V_BATT") (pin "1") (pinfunction "1_1") (pintype "passive"))
    )
    (net (code "19") (name "/V_USB") (class "Default")
      (node (ref "C15") (pin "1") (pinfunction "1_1") (pintype "passive"))
      (node (ref "C16") (pin "2") (pinfunction "2_2") (pintype "passive"))
      (node (ref "C17") (pin "2") (pinfunction "2_2") (pintype "passive"))
      (node (ref "C23") (pin "2") (pinfunction "2_2") (pintype "passive"))
      (node (ref "D1") (pin "A") (pinfunction "A_A") (pintype "passive"))
      (node (ref "J1") (pin "1") (pinfunction "Vcc_1") (pintype "passive"))
      (node (ref "R24") (pin "1") (pinfunction "1_1") (pintype "passive"))
      (node (ref "U6") (pin "10") (pinfunction "VCC_10") (pintype "power_in"))
      (node (ref "U8") (pin "2") (pinfunction "A_2") (pintype "input"))
      (node (ref "U8") (pin "5") (pinfunction "VCC_5") (pintype "power_in"))
      (node (ref "V_USB") (pin "1") (pinfunction "1_1") (pintype "passive"))
    )
    (net (code "20") (name "/XRES") (class "Default")
      (node (ref "U3") (pin "15") (pinfunction "XRES_15") (pintype "bidirectional"))
      (node (ref "XRES") (pin "1") (pinfunction "1_1") (pintype "passive"))
    )
    (net (code "21") (name "GND") (class "Default")
      (node (ref "C1") (pin "2") (pinfunction "2_2") (pintype "passive"))
      (node (ref "C10") (pin "2") (pinfunction "2_2") (pintype "passive"))
      (node (ref "C11") (pin "2") (pinfunction "2_2") (pintype "passive"))
      (node (ref "C12") (pin "2") (pinfunction "2_2") (pintype "passive"))
      (node (ref "C13") (pin "2") (pinfunction "2_2") (pintype "passive"))
      (node (ref "C14") (pin "2") (pinfunction "2_2") (pintype "passive"))
      (node (ref "C15") (pin "2") (pinfunction "2_2") (pintype "passive"))
      (node (ref "C16") (pin "1") (pinfunction "1_1") (pintype "passive"))
      (node (ref "C17") (pin "1") (pinfunction "1_1") (pintype "passive"))
      (node (ref "C18") (pin "2") (pinfunction "2_2") (pintype "passive"))
      (node (ref "C19") (pin "1") (pinfunction "1_1") (pintype "passive"))
      (node (ref "C2") (pin "2") (pinfunction "2_2") (pintype "passive"))
      (node (ref "C20") (pin "2") (pinfunction "2_2") (pintype "passive"))
      (node (ref "C21") (pin "1") (pinfunction "1_1") (pintype "passive"))
      (node (ref "C22") (pin "1") (pinfunction "1_1") (pintype "passive"))
      (node (ref "C23") (pin "1") (pinfunction "1_1") (pintype "passive"))
      (node (ref "C24") (pin "2") (pinfunction "2_2") (pintype "passive"))
      (node (ref "C25") (pin "2") (pinfunction "2_2") (pintype "passive"))
      (node (ref "C3") (pin "1") (pinfunction "1_1") (pintype "passive"))
      (node (ref "C4") (pin "1") (pinfunction "1_1") (pintype "passive"))
      (node (ref "C5") (pin "1") (pinfunction "1_1") (pintype "passive"))
      (node (ref "C6") (pin "2") (pinfunction "2_2") (pintype "passive"))
      (node (ref "C7") (pin "2") (pinfunction "2_2") (pintype "passive"))
      (node (ref "C8") (pin "2") (pinfunction "2_2") (pintype "passive"))
      (node (ref "C9") (pin "2") (pinfunction "2_2") (pintype "passive"))
      (node (ref "GND") (pin "1") (pinfunction "1_1") (pintype "passive"))
      (node (ref "J1") (pin "5") (pinfunction "GND_5") (pintype "passive"))
      (node (ref "J2") (pin "2") (pinfunction "2_2") (pintype "passive"))
      (node (ref "J3") (pin "6") (pinfunction "GND_6") (pintype "passive"))
      (node (ref "R10") (pin "2") (pinfunction "2_2") (pintype "passive"))
      (node (ref "R11") (pin "2") (pinfunction "2_2") (pintype "passive"))
      (node (ref "R15") (pin "1") (pinfunction "1_1") (pintype "passive"))
      (node (ref "R16") (pin "1") (pinfunction "1_1") (pintype "passive"))
      (node (ref "R17") (pin "1") (pinfunction "1_1") (pintype "passive"))
      (node (ref "R21") (pin "2") (pinfunction "2_2") (pintype "passive"))
      (node (ref "R24") (pin "2") (pinfunction "2_2") (pintype "passive"))
      (node (ref "U1") (pin "14") (pinfunction "RES_14") (pintype "passive"))
      (node (ref "U1") (pin "15") (pinfunction "RES_15") (pintype "passive"))
      (node (ref "U1") (pin "16") (pinfunction "RES_16") (pintype "passive"))
      (node (ref "U1") (pin "17") (pinfunction "RES_17") (pintype "passive"))
      (node (ref "U1") (pin "18") (pinfunction "RES_18") (pintype "passive"))
      (node (ref "U1") (pin "19") (pinfunction "GND_19") (pintype "power_in"))
      (node (ref "U1") (pin "20") (pinfunction "GND_20") (pintype "power_in"))
      (node (ref "U2") (pin "13") (pinfunction "GND_13") (pintype "power_in"))
      (node (ref "U2") (pin "17") (pinfunction "EP_17") (pintype "power_in"))
      (node (ref "U2") (pin "3") (pinfunction "GND_3") (pintype "power_in"))
      (node (ref "U3") (pin "1") (pinfunction "GND_1") (pintype "power_in"))
      (node (ref "U3") (pin "11") (pinfunction "GND_11") (pintype "power_in"))
      (node (ref "U4") (pin "2") (pinfunction "GND_2") (pintype "passive"))
      (node (ref "U4") (pin "4") (pinfunction "ADD0_4") (pintype "passive"))
      (node (ref "U4") (pin "7") (pinfunction "GND_7") (pintype "passive"))
      (node (ref "U5") (pin "1") (pinfunction "GND_1") (pintype "passive"))
      (node (ref "U6") (pin "11") (pinfunction "EP_11") (pintype "power_in"))
      (node (ref "U7") (pin "1") (pinfunction "CTG_1") (pintype "passive"))
      (node (ref "U7") (pin "4") (pinfunction "GND_4") (pintype "passive"))
      (node (ref "U7") (pin "6") (pinfunction "QSTRT_6") (pintype "passive"))
      (node (ref "U7") (pin "9") (pinfunction "EP_9") (pintype "passive"))
      (node (ref "U8") (pin "3") (pinfunction "GND_3") (pintype "power_in"))
      (node (ref "U9") (pin "3") (pinfunction "GND_3") (pintype "power_in"))
    )
    (net (code "22") (name "Net-(D1-PadK)") (class "Default")
      (node (ref "D1") (pin "K") (pinfunction "K_K") (pintype "passive"))
      (node (ref "R1") (pin "1") (pinfunction "1_1") (pintype "passive"))
    )
    (net (code "23") (name "Net-(D2-PadK)") (class "Default")
      (node (ref "D2") (pin "K") (pinfunction "K_K") (pintype "passive"))
      (node (ref "R15") (pin "2") (pinfunction "2_2") (pintype "passive"))
    )
    (net (code "24") (name "Net-(D3-PadK)") (class "Default")
      (node (ref "D3") (pin "K") (pinfunction "K_K") (pintype "passive"))
      (node (ref "R16") (pin "2") (pinfunction "2_2") (pintype "passive"))
    )
    (net (code "25") (name "Net-(D4-PadK)") (class "Default")
      (node (ref "D4") (pin "K") (pinfunction "K_K") (pintype "passive"))
      (node (ref "R17") (pin "2") (pinfunction "2_2") (pintype "passive"))
    )
    (net (code "26") (name "Net-(J1-D+)") (class "Default")
      (node (ref "J1") (pin "3") (pinfunction "D+_3") (pintype "passive"))
      (node (ref "R5") (pin "1") (pinfunction "1_1") (pintype "passive"))
    )
    (net (code "27") (name "Net-(J1-D-)") (class "Default")
      (node (ref "J1") (pin "2") (pinfunction "D-_2") (pintype "passive"))
      (node (ref "R6") (pin "1") (pinfunction "1_1") (pintype "passive"))
    )
    (net (code "28") (name "Net-(J3-DAT1)") (class "Default")
      (node (ref "J3") (pin "8") (pinfunction "DAT1_8") (pintype "passive"))
      (node (ref "R19") (pin "2") (pinfunction "2_2") (pintype "passive"))
    )
    (net (code "29") (name "Net-(J3-DAT2)") (class "Default")
      (node (ref "J3") (pin "1") (pinfunction "DAT2_1") (pintype "passive"))
      (node (ref "R7") (pin "2") (pinfunction "2_2") (pintype "passive"))
    )
    (net (code "30") (name "Net-(R21-Pad1)") (class "Default")
      (node (ref "R21") (pin "1") (pinfunction "1_1") (pintype "passive"))
      (node (ref "R22") (pin "1") (pinfunction "1_1") (pintype "passive"))
      (node (ref "SW1") (pin "2") (pinfunction "2_2") (pintype "passive"))
    )
    (net (code "31") (name "Net-(U1-C1)") (class "Default")
      (node (ref "C6") (pin "1") (pinfunction "1_1") (pintype "passive"))
      (node (ref "U1") (pin "24") (pinfunction "C1_24") (pintype "passive"))
    )
    (net (code "32") (name "Net-(U1-CAP)") (class "Default")
      (node (ref "C7") (pin "1") (pinfunction "1_1") (pintype "passive"))
      (node (ref "U1") (pin "21") (pinfunction "CAP_21") (pintype "passive"))
    )
    (net (code "33") (name "Net-(U2-USBDM)") (class "Default")
      (node (ref "C3") (pin "2") (pinfunction "2_2") (pintype "passive"))
      (node (ref "R5") (pin "2") (pinfunction "2_2") (pintype "passive"))
      (node (ref "U2") (pin "7") (pinfunction "USBDM_7") (pintype "input"))
    )
    (net (code "34") (name "Net-(U2-USBDP)") (class "Default")
      (node (ref "C4") (pin "2") (pinfunction "2_2") (pintype "passive"))
      (node (ref "R6") (pin "2") (pinfunction "2_2") (pintype "passive"))
      (node (ref "U2") (pin "6") (pinfunction "USBDP_6") (pintype "input"))
    )
    (net (code "35") (name "Net-(U6-FB)") (class "Default")
      (node (ref "R10") (pin "1") (pinfunction "1_1") (pintype "passive"))
      (node (ref "R9") (pin "1") (pinfunction "1_1") (pintype "passive"))
      (node (ref "U6") (pin "3") (pinfunction "FB_3") (pintype "input"))
    )
    (net (code "36") (name "Net-(U6-IDET)") (class "Default")
      (node (ref "R11") (pin "1") (pinfunction "1_1") (pintype "passive"))
      (node (ref "U6") (pin "8") (pinfunction "IDET_8") (pintype "input"))
      (node (ref "U6") (pin "9") (pinfunction "PROG_9") (pintype "input"))
    )
    (net (code "37") (name "Net-(U6-TIMER)") (class "Default")
      (node (ref "C25") (pin "1") (pinfunction "1_1") (pintype "passive"))
      (node (ref "U6") (pin "7") (pinfunction "TIMER_7") (pintype "input"))
    )
    (net (code "38") (name "Net-(U6-~{CHRG})") (class "Default")
      (node (ref "R1") (pin "2") (pinfunction "2_2") (pintype "passive"))
      (node (ref "U6") (pin "6") (pinfunction "~{CHRG}_6") (pintype "tri_state"))
    )
    (net (code "39") (name "Net-(U7-CELL)") (class "Default")
      (node (ref "C11") (pin "1") (pinfunction "1_1") (pintype "passive"))
      (node (ref "R2") (pin "1") (pinfunction "1_1") (pintype "passive"))
      (node (ref "U7") (pin "2") (pinfunction "CELL_2") (pintype "passive"))
    )
    (net (code "40") (name "Net-(U7-VDD)") (class "Default")
      (node (ref "C10") (pin "1") (pinfunction "1_1") (pintype "passive"))
      (node (ref "R3") (pin "1") (pinfunction "1_1") (pintype "passive"))
      (node (ref "U7") (pin "3") (pinfunction "VDD_3") (pintype "passive"))
    )
    (net (code "41") (name "Net-(U9-D)") (class "Default")
      (node (ref "R23") (pin "1") (pinfunction "1_1") (pintype "passive"))
      (node (ref "U9") (pin "1") (pinfunction "D_1") (pintype "input"))
    )
    (net (code "42") (name "unconnected-(J1-ID-Pad4)") (class "Default")
      (node (ref "J1") (pin "4") (pinfunction "ID_4") (pintype "passive+no_connect"))
    )
    (net (code "43") (name "unconnected-(U1-CS_A{slash}G-Pad7)") (class "Default")
      (node (ref "U1") (pin "7") (pinfunction "CS_A/G_7") (pintype "input+no_connect"))
    )
    (net (code "44") (name "unconnected-(U1-CS_M-Pad8)") (class "Default")
      (node (ref "U1") (pin "8") (pinfunction "CS_M_8") (pintype "input+no_connect"))
    )
    (net (code "45") (name "unconnected-(U1-DEN_A{slash}G-Pad13)") (class "Default")
      (node (ref "U1") (pin "13") (pinfunction "DEN_A/G_13") (pintype "input+no_connect"))
    )
    (net (code "46") (name "unconnected-(U1-DRDY_M-Pad9)") (class "Default")
      (node (ref "U1") (pin "9") (pinfunction "DRDY_M_9") (pintype "output+no_connect"))
    )
    (net (code "47") (name "unconnected-(U1-INT1_A{slash}G-Pad11)") (class "Default")
      (node (ref "U1") (pin "11") (pinfunction "INT1_A/G_11") (pintype "output+no_connect"))
    )
    (net (code "48") (name "unconnected-(U1-INT2_A{slash}G-Pad12)") (class "Default")
      (node (ref "U1") (pin "12") (pinfunction "INT2_A/G_12") (pintype "output+no_connect"))
    )
    (net (code "49") (name "unconnected-(U1-INT_M-Pad10)") (class "Default")
      (node (ref "U1") (pin "10") (pinfunction "INT_M_10") (pintype "output+no_connect"))
    )
    (net (code "50") (name "unconnected-(U2-CBUS0-Pad12)") (class "Default")
      (node (ref "U2") (pin "12") (pinfunction "CBUS0_12") (pintype "bidirectional+no_connect"))
    )
    (net (code "51") (name "unconnected-(U2-CBUS1-Pad11)") (class "Default")
      (node (ref "U2") (pin "11") (pinfunction "CBUS1_11") (pintype "bidirectional+no_connect"))
    )
    (net (code "52") (name "unconnected-(U2-CBUS2-Pad5)") (class "Default")
      (node (ref "U2") (pin "5") (pinfunction "CBUS2_5") (pintype "bidirectional+no_connect"))
    )
    (net (code "53") (name "unconnected-(U2-CBUS3-Pad14)") (class "Default")
      (node (ref "U2") (pin "14") (pinfunction "CBUS3_14") (pintype "bidirectional+no_connect"))
    )
    (net (code "54") (name "unconnected-(U2-CBUS4-Pad4)") (class "Default")
      (node (ref "U2") (pin "4") (pinfunction "CBUS4_4") (pintype "input+no_connect"))
    )
    (net (code "55") (name "unconnected-(U2-CBUS5-Pad15)") (class "Default")
      (node (ref "U2") (pin "15") (pinfunction "CBUS5_15") (pintype "output+no_connect"))
    )
    (net (code "56") (name "unconnected-(U2-RESET#-Pad9)") (class "Default")
      (node (ref "U2") (pin "9") (pinfunction "RESET#_9") (pintype "passive+no_connect"))
    )
    (net (code "57") (name "unconnected-(U3-P4.1-Pad2)") (class "Default")
      (node (ref "U3") (pin "2") (pinfunction "P4.1_2") (pintype "bidirectional+no_connect"))
    )
    (net (code "58") (name "unconnected-(U3-P5.0-Pad4)") (class "Default")
      (node (ref "U3") (pin "4") (pinfunction "P5.0_4") (pintype "bidirectional+no_connect"))
    )
    (net (code "59") (name "unconnected-(U3-P5.1-Pad3)") (class "Default")
      (node (ref "U3") (pin "3") (pinfunction "P5.1_3") (pintype "bidirectional+no_connect"))
    )
    (net (code "60") (name "unconnected-(U3-VREF-Pad6)") (class "Default")
      (node (ref "U3") (pin "6") (pinfunction "VREF_6") (pintype "power_in+no_connect"))
    )
    (net (code "61") (name "unconnected-(U4-ALERT-Pad3)") (class "Default")
      (node (ref "U4") (pin "3") (pinfunction "ALERT_3") (pintype "passive+no_connect"))
    )
    (net (code "62") (name "unconnected-(U8-NC-Pad1)") (class "Default")
      (node (ref "U8") (pin "1") (pinfunction "NC_1") (pintype "passive+no_connect"))
    )
  )
)
